# Input_Filter.net
KiCad netlist of a schematic drawn in Altium Designer
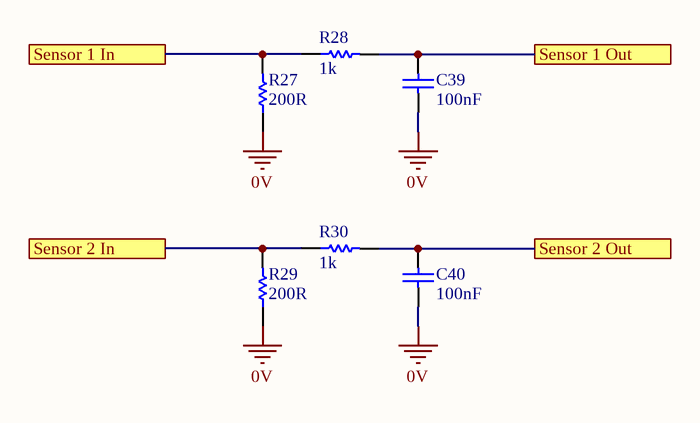
[diagram p0: Input Filter.SchDoc]

(export (version "E")
  (design (tool "Eeschema 10.0.6"))
  (components
    (comp (ref "C39")
      (value "100nF")
      (footprint "0805")
      (fields
        (field (name "PART NUMBER") "GCM21BR71H104KA37L")
        (field (name "TOLERANCE") "±10%")
        (field (name "MANUFACTURER") "muRata")
      )
      (libsource (lib "ts_20-standard-library") (part "Capacitor"))
    )
    (comp (ref "C40")
      (value "100nF")
      (footprint "0805")
      (fields
        (field (name "PART NUMBER") "GCM21BR71H104KA37L")
        (field (name "TOLERANCE") "±10%")
        (field (name "MANUFACTURER") "muRata")
      )
      (libsource (lib "ts_20-standard-library") (part "Capacitor"))
    )
    (comp (ref "R27")
      (value "200R")
      (footprint "0805")
      (fields
        (field (name "PART NUMBER") "RC0805FR07200RL")
        (field (name "MANUFACTURER") "YAGEO")
        (field (name "TOLERANCE") "0.01")
      )
      (libsource (lib "ts_20-standard-library") (part "Resistor"))
    )
    (comp (ref "R28")
      (value "1k")
      (footprint "0805")
      (fields
        (field (name "PART NUMBER") "RC0805FR071KL")
        (field (name "MANUFACTURER") "YAGEO")
        (field (name "TOLERANCE") "0.01")
      )
      (libsource (lib "ts_20-standard-library") (part "Resistor"))
    )
    (comp (ref "R29")
      (value "200R")
      (footprint "0805")
      (fields
        (field (name "PART NUMBER") "RC0805FR07200RL")
        (field (name "MANUFACTURER") "YAGEO")
        (field (name "TOLERANCE") "0.01")
      )
      (libsource (lib "ts_20-standard-library") (part "Resistor"))
    )
    (comp (ref "R30")
      (value "1k")
      (footprint "0805")
      (fields
        (field (name "PART NUMBER") "RC0805FR071KL")
        (field (name "MANUFACTURER") "YAGEO")
        (field (name "TOLERANCE") "0.01")
      )
      (libsource (lib "ts_20-standard-library") (part "Resistor"))
    )
  )
  (nets
    (net (code "1") (name "/Sensor 1 In") (class "Default")
      (node (ref "R27") (pin "2") (pinfunction "2_2") (pintype "passive"))
      (node (ref "R28") (pin "1") (pinfunction "1_1") (pintype "passive"))
    )
    (net (code "2") (name "/Sensor 1 Out") (class "Default")
      (node (ref "C39") (pin "2") (pinfunction "2_2") (pintype "passive"))
      (node (ref "R28") (pin "2") (pinfunction "2_2") (pintype "passive"))
    )
    (net (code "3") (name "/Sensor 2 In") (class "Default")
      (node (ref "R29") (pin "2") (pinfunction "2_2") (pintype "passive"))
      (node (ref "R30") (pin "1") (pinfunction "1_1") (pintype "passive"))
    )
    (net (code "4") (name "/Sensor 2 Out") (class "Default")
      (node (ref "C40") (pin "2") (pinfunction "2_2") (pintype "passive"))
      (node (ref "R30") (pin "2") (pinfunction "2_2") (pintype "passive"))
    )
    (net (code "5") (name "0V") (class "Default")
      (node (ref "C39") (pin "1") (pinfunction "1_1") (pintype "passive"))
      (node (ref "C40") (pin "1") (pinfunction "1_1") (pintype "passive"))
      (node (ref "R27") (pin "1") (pinfunction "1_1") (pintype "passive"))
      (node (ref "R29") (pin "1") (pinfunction "1_1") (pintype "passive"))
    )
  )
)
